# M20DX256_Eval_Board.net
KiCad netlist of a schematic drawn in EAGLE
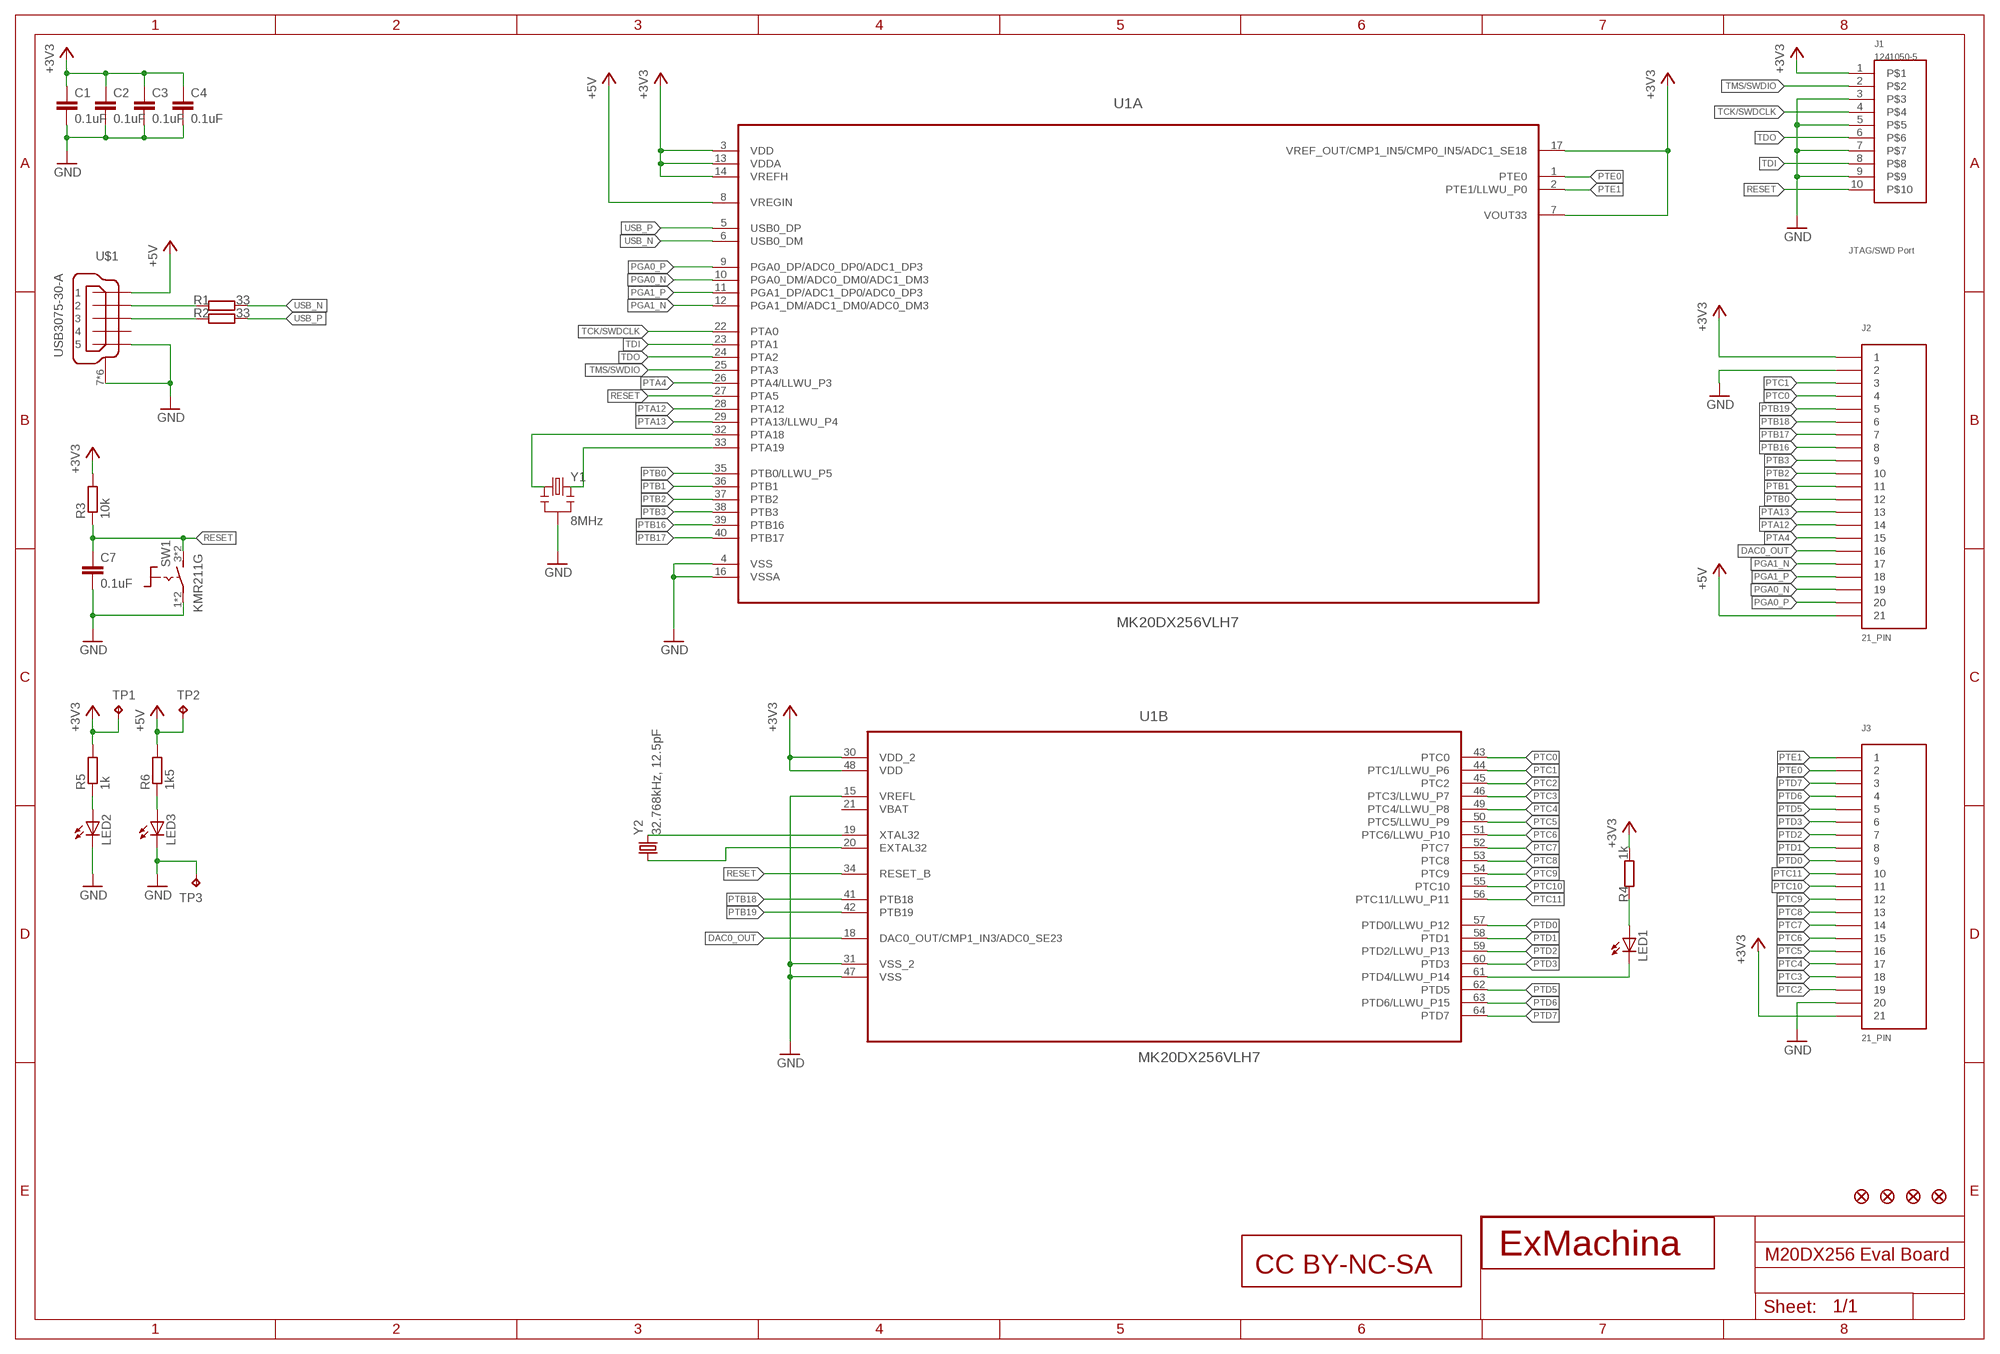
[diagram p0: schematic, sheet 1]

(export (version "E")
  (design (tool "Eeschema 10.0.6"))
  (components
    (comp (ref "C1")
      (value "0.1uF")
      (footprint "eagle-import:C0603")
      (fields (field (name "MPN") "MC0603B104K160CT"))
      (libsource (lib "eagle-import") (part "C-EUC0603"))
    )
    (comp (ref "C2")
      (value "0.1uF")
      (footprint "eagle-import:C0603")
      (fields (field (name "MPN") "MC0603B104K160CT"))
      (libsource (lib "eagle-import") (part "C-EUC0603"))
    )
    (comp (ref "C3")
      (value "0.1uF")
      (footprint "eagle-import:C0603")
      (fields (field (name "MPN") "MC0603B104K160CT"))
      (libsource (lib "eagle-import") (part "C-EUC0603"))
    )
    (comp (ref "C4")
      (value "0.1uF")
      (footprint "eagle-import:C0603")
      (fields (field (name "MPN") "MC0603B104K160CT"))
      (libsource (lib "eagle-import") (part "C-EUC0603"))
    )
    (comp (ref "C7")
      (value "0.1uF")
      (footprint "eagle-import:C0603")
      (fields (field (name "MPN") "MC0603B104K160CT"))
      (libsource (lib "eagle-import") (part "C-EUC0603"))
    )
    (comp (ref "J1")
      (value "1241050-5")
      (footprint "eagle-import:2.54_2X5")
      (libsource (lib "eagle-import") (part "1241050-5"))
    )
    (comp (ref "J2")
      (value "21_PIN")
      (footprint "eagle-import:21_CUSTOM")
      (libsource (lib "eagle-import") (part "21_PIN"))
    )
    (comp (ref "J3")
      (value "21_PIN")
      (footprint "eagle-import:21_CUSTOM")
      (libsource (lib "eagle-import") (part "21_PIN"))
    )
    (comp (ref "JP1")
      (value "FIDUCIAL1X2")
      (footprint "eagle-import:FIDUCIAL-1X2")
      (libsource (lib "eagle-import") (part "FIDUCIAL1X2"))
    )
    (comp (ref "JP2")
      (value "FIDUCIAL1X2")
      (footprint "eagle-import:FIDUCIAL-1X2")
      (libsource (lib "eagle-import") (part "FIDUCIAL1X2"))
    )
    (comp (ref "JP3")
      (value "FIDUCIAL1X2")
      (footprint "eagle-import:FIDUCIAL-1X2")
      (libsource (lib "eagle-import") (part "FIDUCIAL1X2"))
    )
    (comp (ref "JP4")
      (value "FIDUCIAL1X2")
      (footprint "eagle-import:FIDUCIAL-1X2")
      (libsource (lib "eagle-import") (part "FIDUCIAL1X2"))
    )
    (comp (ref "LED1")
      (value "LEDCHIP-LED0603")
      (footprint "eagle-import:CHIP-LED0603")
      (libsource (lib "eagle-import") (part "LEDCHIP-LED0603"))
    )
    (comp (ref "LED2")
      (value "LEDCHIP-LED0603")
      (footprint "eagle-import:CHIP-LED0603")
      (libsource (lib "eagle-import") (part "LEDCHIP-LED0603"))
    )
    (comp (ref "LED3")
      (value "LEDCHIP-LED0603")
      (footprint "eagle-import:CHIP-LED0603")
      (libsource (lib "eagle-import") (part "LEDCHIP-LED0603"))
    )
    (comp (ref "R1")
      (value "33")
      (footprint "eagle-import:R0603")
      (fields (field (name "MPN") "MCMR06X33R0FTL"))
      (libsource (lib "eagle-import") (part "R-EU_R0603"))
    )
    (comp (ref "R2")
      (value "33")
      (footprint "eagle-import:R0603")
      (fields (field (name "MPN") "MCMR06X33R0FTL"))
      (libsource (lib "eagle-import") (part "R-EU_R0603"))
    )
    (comp (ref "R3")
      (value "10k")
      (footprint "eagle-import:R0603")
      (fields (field (name "MPN") "MCMR06X1002FTL"))
      (libsource (lib "eagle-import") (part "R-EU_R0603"))
    )
    (comp (ref "R4")
      (value "1k")
      (footprint "eagle-import:R0603")
      (fields (field (name "MPN") "MCMR06X1001FTL"))
      (libsource (lib "eagle-import") (part "R-EU_R0603"))
    )
    (comp (ref "R5")
      (value "1k")
      (footprint "eagle-import:R0603")
      (fields (field (name "MPN") "MCMR06X1001FTL"))
      (libsource (lib "eagle-import") (part "R-EU_R0603"))
    )
    (comp (ref "R6")
      (value "1k5")
      (footprint "eagle-import:R0603")
      (fields (field (name "MPN") "MCMR06X1501FTL"))
      (libsource (lib "eagle-import") (part "R-EU_R0603"))
    )
    (comp (ref "SW1")
      (value "KMR211G")
      (footprint "eagle-import:KM_SERIE")
      (fields (field (name "MPN") "KMR211G LFS"))
      (libsource (lib "eagle-import") (part "KMR211G"))
    )
    (comp (ref "TP1")
      (value "TPB1,27")
      (footprint "eagle-import:B1,27")
      (libsource (lib "eagle-import") (part "TPB1,27"))
    )
    (comp (ref "TP2")
      (value "TPB1,27")
      (footprint "eagle-import:B1,27")
      (libsource (lib "eagle-import") (part "TPB1,27"))
    )
    (comp (ref "TP3")
      (value "TPB1,27")
      (footprint "eagle-import:B1,27")
      (libsource (lib "eagle-import") (part "TPB1,27"))
    )
    (comp (ref "U$1")
      (value "USB3075-30-A")
      (footprint "eagle-import:USB_MICROB_SMT")
      (libsource (lib "eagle-import") (part "USB3075-30-A"))
    )
    (comp (ref "U$3")
      (value "EXMACHINA-LOGO-NAME")
      (footprint "eagle-import:EXM-LOGO-BASELINE")
      (libsource (lib "eagle-import") (part "EXMACHINA-LOGO-NAME"))
    )
    (comp (ref "U$4")
      (value "CC-BY-NC-SA")
      (footprint "eagle-import:CC-BY-NC-SA")
      (libsource (lib "eagle-import") (part "CC-BY-NC-SA"))
    )
    (comp (ref "U1")
      (value "MK20DX256VLH7")
      (footprint "eagle-import:QFP50P1200X1200X160-64N")
      (libsource (lib "eagle-import") (part "MK20DX256VLH7"))
    )
    (comp (ref "Y1")
      (value "8MHz")
      (footprint "eagle-import:RESONATOR-SMD")
      (fields (field (name "MPN") "CSTCE8M00G55Z-R0"))
      (libsource (lib "eagle-import") (part "RESONATORSMD"))
    )
    (comp (ref "Y2")
      (value "32.768kHz, 12.5pF")
      (footprint "eagle-import:ABS07")
      (fields (field (name "MPN") "ABS07-32.768KHZ-1-T"))
      (libsource (lib "eagle-import") (part "ABS07-?32.768KHZ"))
    )
  )
  (nets
    (net (code "1") (name "+3V3") (class "Default")
      (node (ref "C1") (pin "1") (pinfunction "1_1") (pintype "passive"))
      (node (ref "C2") (pin "1") (pinfunction "1_1") (pintype "passive"))
      (node (ref "C3") (pin "1") (pinfunction "1_1") (pintype "passive"))
      (node (ref "C4") (pin "1") (pinfunction "1_1") (pintype "passive"))
      (node (ref "J1") (pin "1") (pinfunction "P$1_1") (pintype "bidirectional"))
      (node (ref "J2") (pin "P$1") (pinfunction "1_P$1") (pintype "bidirectional"))
      (node (ref "J3") (pin "P$21") (pinfunction "21_P$21") (pintype "bidirectional"))
      (node (ref "R3") (pin "2") (pinfunction "2_2") (pintype "passive"))
      (node (ref "R4") (pin "2") (pinfunction "2_2") (pintype "passive"))
      (node (ref "R5") (pin "2") (pinfunction "2_2") (pintype "passive"))
      (node (ref "TP1") (pin "TP") (pinfunction "TP_TP") (pintype "input"))
      (node (ref "U1") (pin "13") (pinfunction "VDDA_13") (pintype "power_in"))
      (node (ref "U1") (pin "14") (pinfunction "VREFH_14") (pintype "passive"))
      (node (ref "U1") (pin "17") (pinfunction "VREF_OUT/CMP1_IN5/CMP0_IN5/ADC1_SE18_17") (pintype "output"))
      (node (ref "U1") (pin "3") (pinfunction "VDD_3") (pintype "power_in"))
      (node (ref "U1") (pin "30") (pinfunction "VDD_2_30") (pintype "power_in"))
      (node (ref "U1") (pin "48") (pinfunction "VDD_48") (pintype "power_in"))
      (node (ref "U1") (pin "7") (pinfunction "VOUT33_7") (pintype "output"))
    )
    (net (code "2") (name "+5V") (class "Default")
      (node (ref "J2") (pin "P$21") (pinfunction "21_P$21") (pintype "bidirectional"))
      (node (ref "R6") (pin "2") (pinfunction "2_2") (pintype "passive"))
      (node (ref "TP2") (pin "TP") (pinfunction "TP_TP") (pintype "input"))
      (node (ref "U$1") (pin "1") (pinfunction "1_1") (pintype "passive"))
      (node (ref "U1") (pin "8") (pinfunction "VREGIN_8") (pintype "input"))
    )
    (net (code "3") (name "/VBAT") (class "Default")
      (node (ref "U1") (pin "21") (pinfunction "VBAT_21") (pintype "power_in"))
    )
    (net (code "4") (name "DAC0_OUT") (class "Default")
      (node (ref "J2") (pin "P$16") (pinfunction "16_P$16") (pintype "bidirectional"))
      (node (ref "U1") (pin "18") (pinfunction "DAC0_OUT/CMP1_IN3/ADC0_SE23_18") (pintype "passive"))
    )
    (net (code "5") (name "GND") (class "Default")
      (node (ref "C1") (pin "2") (pinfunction "2_2") (pintype "passive"))
      (node (ref "C2") (pin "2") (pinfunction "2_2") (pintype "passive"))
      (node (ref "C3") (pin "2") (pinfunction "2_2") (pintype "passive"))
      (node (ref "C4") (pin "2") (pinfunction "2_2") (pintype "passive"))
      (node (ref "C7") (pin "2") (pinfunction "2_2") (pintype "passive"))
      (node (ref "J1") (pin "3") (pinfunction "P$3_3") (pintype "bidirectional"))
      (node (ref "J1") (pin "5") (pinfunction "P$5_5") (pintype "bidirectional"))
      (node (ref "J1") (pin "7") (pinfunction "P$7_7") (pintype "bidirectional"))
      (node (ref "J1") (pin "9") (pinfunction "P$9_9") (pintype "bidirectional"))
      (node (ref "J2") (pin "P$2") (pinfunction "2_P$2") (pintype "bidirectional"))
      (node (ref "J3") (pin "P$20") (pinfunction "20_P$20") (pintype "bidirectional"))
      (node (ref "LED2") (pin "C") (pinfunction "C_C") (pintype "passive"))
      (node (ref "LED3") (pin "C") (pinfunction "C_C") (pintype "passive"))
      (node (ref "SW1") (pin "1") (pinfunction "2_1") (pintype "passive"))
      (node (ref "SW1") (pin "2") (pinfunction "2_2") (pintype "passive"))
      (node (ref "TP3") (pin "TP") (pinfunction "TP_TP") (pintype "input"))
      (node (ref "U$1") (pin "10") (pinfunction "S_10") (pintype "bidirectional"))
      (node (ref "U$1") (pin "11") (pinfunction "S_11") (pintype "bidirectional"))
      (node (ref "U$1") (pin "12") (pinfunction "S_12") (pintype "bidirectional"))
      (node (ref "U$1") (pin "5") (pinfunction "5_5") (pintype "passive"))
      (node (ref "U$1") (pin "7") (pinfunction "S_7") (pintype "bidirectional"))
      (node (ref "U$1") (pin "8") (pinfunction "S_8") (pintype "bidirectional"))
      (node (ref "U$1") (pin "9") (pinfunction "S_9") (pintype "bidirectional"))
      (node (ref "U1") (pin "15") (pinfunction "VREFL_15") (pintype "passive"))
      (node (ref "U1") (pin "16") (pinfunction "VSSA_16") (pintype "passive"))
      (node (ref "U1") (pin "31") (pinfunction "VSS_2_31") (pintype "passive"))
      (node (ref "U1") (pin "4") (pinfunction "VSS_4") (pintype "passive"))
      (node (ref "U1") (pin "47") (pinfunction "VSS_47") (pintype "passive"))
      (node (ref "Y1") (pin "2") (pinfunction "2_2") (pintype "passive"))
    )
    (net (code "6") (name "Net-(LED1-PadA)") (class "Default")
      (node (ref "LED1") (pin "A") (pinfunction "A_A") (pintype "passive"))
      (node (ref "R4") (pin "1") (pinfunction "1_1") (pintype "passive"))
    )
    (net (code "7") (name "Net-(LED2-PadA)") (class "Default")
      (node (ref "LED2") (pin "A") (pinfunction "A_A") (pintype "passive"))
      (node (ref "R5") (pin "1") (pinfunction "1_1") (pintype "passive"))
    )
    (net (code "8") (name "Net-(LED3-PadA)") (class "Default")
      (node (ref "LED3") (pin "A") (pinfunction "A_A") (pintype "passive"))
      (node (ref "R6") (pin "1") (pinfunction "1_1") (pintype "passive"))
    )
    (net (code "9") (name "Net-(R1-Pad1)") (class "Default")
      (node (ref "R1") (pin "1") (pinfunction "1_1") (pintype "passive"))
      (node (ref "U$1") (pin "2") (pinfunction "2_2") (pintype "passive"))
    )
    (net (code "10") (name "Net-(R2-Pad1)") (class "Default")
      (node (ref "R2") (pin "1") (pinfunction "1_1") (pintype "passive"))
      (node (ref "U$1") (pin "3") (pinfunction "3_3") (pintype "passive"))
    )
    (net (code "11") (name "Net-(U1A-PTA18)") (class "Default")
      (node (ref "U1") (pin "32") (pinfunction "PTA18_32") (pintype "bidirectional"))
      (node (ref "Y1") (pin "1") (pinfunction "1_1") (pintype "passive"))
    )
    (net (code "12") (name "Net-(U1A-PTA19)") (class "Default")
      (node (ref "U1") (pin "33") (pinfunction "PTA19_33") (pintype "bidirectional"))
      (node (ref "Y1") (pin "3") (pinfunction "3_3") (pintype "passive"))
    )
    (net (code "13") (name "Net-(U1B-EXTAL32)") (class "Default")
      (node (ref "U1") (pin "20") (pinfunction "EXTAL32_20") (pintype "passive"))
      (node (ref "Y2") (pin "1") (pinfunction "1_1") (pintype "passive"))
    )
    (net (code "14") (name "Net-(U1B-PTD4{slash}LLWU_P14)") (class "Default")
      (node (ref "LED1") (pin "C") (pinfunction "C_C") (pintype "passive"))
      (node (ref "U1") (pin "61") (pinfunction "PTD4/LLWU_P14_61") (pintype "bidirectional"))
    )
    (net (code "15") (name "Net-(U1B-XTAL32)") (class "Default")
      (node (ref "U1") (pin "19") (pinfunction "XTAL32_19") (pintype "passive"))
      (node (ref "Y2") (pin "2") (pinfunction "2_2") (pintype "passive"))
    )
    (net (code "16") (name "PGA0_N") (class "Default")
      (node (ref "J2") (pin "P$19") (pinfunction "19_P$19") (pintype "bidirectional"))
      (node (ref "U1") (pin "10") (pinfunction "PGA0_DM/ADC0_DM0/ADC1_DM3_10") (pintype "bidirectional"))
    )
    (net (code "17") (name "PGA0_P") (class "Default")
      (node (ref "J2") (pin "P$20") (pinfunction "20_P$20") (pintype "bidirectional"))
      (node (ref "U1") (pin "9") (pinfunction "PGA0_DP/ADC0_DP0/ADC1_DP3_9") (pintype "bidirectional"))
    )
    (net (code "18") (name "PGA1_N") (class "Default")
      (node (ref "J2") (pin "P$17") (pinfunction "17_P$17") (pintype "bidirectional"))
      (node (ref "U1") (pin "12") (pinfunction "PGA1_DM/ADC1_DM0/ADC0_DM3_12") (pintype "bidirectional"))
    )
    (net (code "19") (name "PGA1_P") (class "Default")
      (node (ref "J2") (pin "P$18") (pinfunction "18_P$18") (pintype "bidirectional"))
      (node (ref "U1") (pin "11") (pinfunction "PGA1_DP/ADC1_DP0/ADC0_DP3_11") (pintype "bidirectional"))
    )
    (net (code "20") (name "PTA4") (class "Default")
      (node (ref "J2") (pin "P$15") (pinfunction "15_P$15") (pintype "bidirectional"))
      (node (ref "U1") (pin "26") (pinfunction "PTA4/LLWU_P3_26") (pintype "bidirectional"))
    )
    (net (code "21") (name "PTA12") (class "Default")
      (node (ref "J2") (pin "P$14") (pinfunction "14_P$14") (pintype "bidirectional"))
      (node (ref "U1") (pin "28") (pinfunction "PTA12_28") (pintype "bidirectional"))
    )
    (net (code "22") (name "PTA13") (class "Default")
      (node (ref "J2") (pin "P$13") (pinfunction "13_P$13") (pintype "bidirectional"))
      (node (ref "U1") (pin "29") (pinfunction "PTA13/LLWU_P4_29") (pintype "bidirectional"))
    )
    (net (code "23") (name "PTB0") (class "Default")
      (node (ref "J2") (pin "P$12") (pinfunction "12_P$12") (pintype "bidirectional"))
      (node (ref "U1") (pin "35") (pinfunction "PTB0/LLWU_P5_35") (pintype "bidirectional"))
    )
    (net (code "24") (name "PTB1") (class "Default")
      (node (ref "J2") (pin "P$11") (pinfunction "11_P$11") (pintype "bidirectional"))
      (node (ref "U1") (pin "36") (pinfunction "PTB1_36") (pintype "bidirectional"))
    )
    (net (code "25") (name "PTB2") (class "Default")
      (node (ref "J2") (pin "P$10") (pinfunction "10_P$10") (pintype "bidirectional"))
      (node (ref "U1") (pin "37") (pinfunction "PTB2_37") (pintype "bidirectional"))
    )
    (net (code "26") (name "PTB3") (class "Default")
      (node (ref "J2") (pin "P$9") (pinfunction "9_P$9") (pintype "bidirectional"))
      (node (ref "U1") (pin "38") (pinfunction "PTB3_38") (pintype "bidirectional"))
    )
    (net (code "27") (name "PTB16") (class "Default")
      (node (ref "J2") (pin "P$8") (pinfunction "8_P$8") (pintype "bidirectional"))
      (node (ref "U1") (pin "39") (pinfunction "PTB16_39") (pintype "bidirectional"))
    )
    (net (code "28") (name "PTB17") (class "Default")
      (node (ref "J2") (pin "P$7") (pinfunction "7_P$7") (pintype "bidirectional"))
      (node (ref "U1") (pin "40") (pinfunction "PTB17_40") (pintype "bidirectional"))
    )
    (net (code "29") (name "PTB18") (class "Default")
      (node (ref "J2") (pin "P$6") (pinfunction "6_P$6") (pintype "bidirectional"))
      (node (ref "U1") (pin "41") (pinfunction "PTB18_41") (pintype "bidirectional"))
    )
    (net (code "30") (name "PTB19") (class "Default")
      (node (ref "J2") (pin "P$5") (pinfunction "5_P$5") (pintype "bidirectional"))
      (node (ref "U1") (pin "42") (pinfunction "PTB19_42") (pintype "bidirectional"))
    )
    (net (code "31") (name "PTC0") (class "Default")
      (node (ref "J2") (pin "P$4") (pinfunction "4_P$4") (pintype "bidirectional"))
      (node (ref "U1") (pin "43") (pinfunction "PTC0_43") (pintype "bidirectional"))
    )
    (net (code "32") (name "PTC1") (class "Default")
      (node (ref "J2") (pin "P$3") (pinfunction "3_P$3") (pintype "bidirectional"))
      (node (ref "U1") (pin "44") (pinfunction "PTC1/LLWU_P6_44") (pintype "bidirectional"))
    )
    (net (code "33") (name "PTC2") (class "Default")
      (node (ref "J3") (pin "P$19") (pinfunction "19_P$19") (pintype "bidirectional"))
      (node (ref "U1") (pin "45") (pinfunction "PTC2_45") (pintype "bidirectional"))
    )
    (net (code "34") (name "PTC3") (class "Default")
      (node (ref "J3") (pin "P$18") (pinfunction "18_P$18") (pintype "bidirectional"))
      (node (ref "U1") (pin "46") (pinfunction "PTC3/LLWU_P7_46") (pintype "bidirectional"))
    )
    (net (code "35") (name "PTC4") (class "Default")
      (node (ref "J3") (pin "P$17") (pinfunction "17_P$17") (pintype "bidirectional"))
      (node (ref "U1") (pin "49") (pinfunction "PTC4/LLWU_P8_49") (pintype "bidirectional"))
    )
    (net (code "36") (name "PTC5") (class "Default")
      (node (ref "J3") (pin "P$16") (pinfunction "16_P$16") (pintype "bidirectional"))
      (node (ref "U1") (pin "50") (pinfunction "PTC5/LLWU_P9_50") (pintype "bidirectional"))
    )
    (net (code "37") (name "PTC6") (class "Default")
      (node (ref "J3") (pin "P$15") (pinfunction "15_P$15") (pintype "bidirectional"))
      (node (ref "U1") (pin "51") (pinfunction "PTC6/LLWU_P10_51") (pintype "bidirectional"))
    )
    (net (code "38") (name "PTC7") (class "Default")
      (node (ref "J3") (pin "P$14") (pinfunction "14_P$14") (pintype "bidirectional"))
      (node (ref "U1") (pin "52") (pinfunction "PTC7_52") (pintype "bidirectional"))
    )
    (net (code "39") (name "PTC8") (class "Default")
      (node (ref "J3") (pin "P$13") (pinfunction "13_P$13") (pintype "bidirectional"))
      (node (ref "U1") (pin "53") (pinfunction "PTC8_53") (pintype "bidirectional"))
    )
    (net (code "40") (name "PTC9") (class "Default")
      (node (ref "J3") (pin "P$12") (pinfunction "12_P$12") (pintype "bidirectional"))
      (node (ref "U1") (pin "54") (pinfunction "PTC9_54") (pintype "bidirectional"))
    )
    (net (code "41") (name "PTC10") (class "Default")
      (node (ref "J3") (pin "P$11") (pinfunction "11_P$11") (pintype "bidirectional"))
      (node (ref "U1") (pin "55") (pinfunction "PTC10_55") (pintype "bidirectional"))
    )
    (net (code "42") (name "PTC11") (class "Default")
      (node (ref "J3") (pin "P$10") (pinfunction "10_P$10") (pintype "bidirectional"))
      (node (ref "U1") (pin "56") (pinfunction "PTC11/LLWU_P11_56") (pintype "bidirectional"))
    )
    (net (code "43") (name "PTD0") (class "Default")
      (node (ref "J3") (pin "P$9") (pinfunction "9_P$9") (pintype "bidirectional"))
      (node (ref "U1") (pin "57") (pinfunction "PTD0/LLWU_P12_57") (pintype "bidirectional"))
    )
    (net (code "44") (name "PTD1") (class "Default")
      (node (ref "J3") (pin "P$8") (pinfunction "8_P$8") (pintype "bidirectional"))
      (node (ref "U1") (pin "58") (pinfunction "PTD1_58") (pintype "bidirectional"))
    )
    (net (code "45") (name "PTD2") (class "Default")
      (node (ref "J3") (pin "P$7") (pinfunction "7_P$7") (pintype "bidirectional"))
      (node (ref "U1") (pin "59") (pinfunction "PTD2/LLWU_P13_59") (pintype "bidirectional"))
    )
    (net (code "46") (name "PTD3") (class "Default")
      (node (ref "J3") (pin "P$6") (pinfunction "6_P$6") (pintype "bidirectional"))
      (node (ref "U1") (pin "60") (pinfunction "PTD3_60") (pintype "bidirectional"))
    )
    (net (code "47") (name "PTD5") (class "Default")
      (node (ref "J3") (pin "P$5") (pinfunction "5_P$5") (pintype "bidirectional"))
      (node (ref "U1") (pin "62") (pinfunction "PTD5_62") (pintype "bidirectional"))
    )
    (net (code "48") (name "PTD6") (class "Default")
      (node (ref "J3") (pin "P$4") (pinfunction "4_P$4") (pintype "bidirectional"))
      (node (ref "U1") (pin "63") (pinfunction "PTD6/LLWU_P15_63") (pintype "bidirectional"))
    )
    (net (code "49") (name "PTD7") (class "Default")
      (node (ref "J3") (pin "P$3") (pinfunction "3_P$3") (pintype "bidirectional"))
      (node (ref "U1") (pin "64") (pinfunction "PTD7_64") (pintype "bidirectional"))
    )
    (net (code "50") (name "PTE0") (class "Default")
      (node (ref "J3") (pin "P$2") (pinfunction "2_P$2") (pintype "bidirectional"))
      (node (ref "U1") (pin "1") (pinfunction "PTE0_1") (pintype "bidirectional"))
    )
    (net (code "51") (name "PTE1") (class "Default")
      (node (ref "J3") (pin "P$1") (pinfunction "1_P$1") (pintype "bidirectional"))
      (node (ref "U1") (pin "2") (pinfunction "PTE1/LLWU_P0_2") (pintype "bidirectional"))
    )
    (net (code "52") (name "RESET") (class "Default")
      (node (ref "C7") (pin "1") (pinfunction "1_1") (pintype "passive"))
      (node (ref "J1") (pin "10") (pinfunction "P$10_10") (pintype "bidirectional"))
      (node (ref "R3") (pin "1") (pinfunction "1_1") (pintype "passive"))
      (node (ref "SW1") (pin "3") (pinfunction "1_3") (pintype "passive"))
      (node (ref "SW1") (pin "4") (pinfunction "1_4") (pintype "passive"))
      (node (ref "U1") (pin "27") (pinfunction "PTA5_27") (pintype "bidirectional"))
      (node (ref "U1") (pin "34") (pinfunction "RESET_B_34") (pintype "passive"))
    )
    (net (code "53") (name "TCK{slash}SWDCLK") (class "Default")
      (node (ref "J1") (pin "4") (pinfunction "P$4_4") (pintype "bidirectional"))
      (node (ref "U1") (pin "22") (pinfunction "PTA0_22") (pintype "bidirectional"))
    )
    (net (code "54") (name "TDI") (class "Default")
      (node (ref "J1") (pin "8") (pinfunction "P$8_8") (pintype "bidirectional"))
      (node (ref "U1") (pin "23") (pinfunction "PTA1_23") (pintype "bidirectional"))
    )
    (net (code "55") (name "TDO") (class "Default")
      (node (ref "J1") (pin "6") (pinfunction "P$6_6") (pintype "bidirectional"))
      (node (ref "U1") (pin "24") (pinfunction "PTA2_24") (pintype "bidirectional"))
    )
    (net (code "56") (name "TMS{slash}SWDIO") (class "Default")
      (node (ref "J1") (pin "2") (pinfunction "P$2_2") (pintype "bidirectional"))
      (node (ref "U1") (pin "25") (pinfunction "PTA3_25") (pintype "bidirectional"))
    )
    (net (code "57") (name "USB_N") (class "Default")
      (node (ref "R1") (pin "2") (pinfunction "2_2") (pintype "passive"))
      (node (ref "U1") (pin "6") (pinfunction "USB0_DM_6") (pintype "passive"))
    )
    (net (code "58") (name "USB_P") (class "Default")
      (node (ref "R2") (pin "2") (pinfunction "2_2") (pintype "passive"))
      (node (ref "U1") (pin "5") (pinfunction "USB0_DP_5") (pintype "passive"))
    )
    (net (code "59") (name "unconnected-(U$1-Pad4)") (class "Default")
      (node (ref "U$1") (pin "4") (pinfunction "4_4") (pintype "passive"))
    )
  )
)
